# SuscoderSCH.net
KiCad netlist of a schematic drawn in Altium Designer
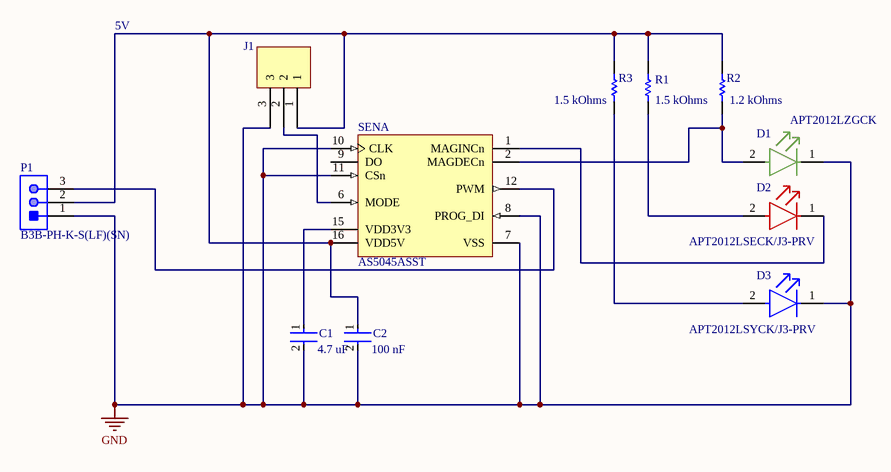
[diagram p0: SuscoderSCH.SchDoc]

(export (version "E")
  (design (tool "Eeschema 10.0.6"))
  (components
    (comp (ref "C1")
      (value "CC0805KKX7R7BB475")
      (footprint "FP-CC0805-0_85-MFG")
      (description "CAP CER 4.7UF 16V X7R 0805")
      (fields
        (field (name "MANUFACTURER") "Yageo")
        (field (name "OCTOPART") "https://octopart.com/cc0805kkx7r7bb475-yageo-34429188")
        (field (name "CAPACITANCE") "4.7 uF")
      )
      (libsource (lib "Altium Content Vault") (part "11868f565c42a9108669ba33697ecf6"))
    )
    (comp (ref "C2")
      (value "CC0805KRX7R7BB104")
      (footprint "FP-CC0805-0_85-MFG")
      (description "CAP CER 0.1UF 16V X7R 0805")
      (fields
        (field (name "MANUFACTURER") "Yageo")
        (field (name "OCTOPART") "https://octopart.com/cc0805krx7r7bb104-yageo-39467769")
        (field (name "CAPACITANCE") "100 nF")
      )
      (libsource (lib "Altium Content Vault") (part "11868f565c42a9108669ba33697ecf6"))
    )
    (comp (ref "D1")
      (value "APT2012LZGCK")
      (footprint "FP-APT2012LSYCK-J3-PRV-MFG")
      (description "2.0X1.2mm Low Current Green SMD LED; Water Clear; 525nm; 140° Viewing Angle")
      (libsource (lib "FRC2021 - #604") (part "8706943c75ba83719d021d2fdc84c58"))
    )
    (comp (ref "D2")
      (value "APT2012LSECK/J3-PRV")
      (footprint "FP-APT2012LSYCK-J3-PRV-MFG")
      (description "2.0X1.2mm Low Current Red SMD LED; Water Clear; 625nm; 140° Viewing Angle")
      (libsource (lib "FRC2021 - #604") (part "8706943c75ba83719d021d2fdc84c58"))
    )
    (comp (ref "D3")
      (value "APT2012LSYCK/J3-PRV")
      (footprint "FP-APT2012LSYCK-J3-PRV-MFG")
      (description "LED YELLOW CLEAR 2SMD")
      (fields
        (field (name "MANUFACTURER") "Kingbright")
        (field (name "OCTOPART") "https://octopart.com/apt2012lsyck%2Fj3-prv-kingbright-56784114")
      )
      (libsource (lib "Altium Content Vault") (part "8706943c75ba83719d021d2fdc84c58"))
    )
    (comp (ref "J1")
      (value "Tri-Pad Jumper")
      (footprint "Tri-Pad Jumper-Footprint-1")
      (description "A jumper with 3 pads.")
      (libsource (lib "FRC2021 - #604") (part "Tri-Pad Jumper-Symbol-1"))
    )
    (comp (ref "P1")
      (value "B3B-PH-K-S(LF)(SN)")
      (footprint "JST-B3B-PH-K-S-3_V")
      (fields (field (name "MANUFACTURER") "JST"))
      (libsource (lib "Altium Content Vault") (part "CN-1P-M-R3"))
    )
    (comp (ref "R1")
      (value "ERJ-6ENF1501V")
      (footprint "RESC2013X70X40ML20T20")
      (fields (field (name "MANUFACTURER") "Panasonic") (field (name "RESISTANCE") "1.5 kOhms"))
      (libsource (lib "Altium Content Vault") (part "RES"))
    )
    (comp (ref "R2")
      (value "ERJ6ENF1201V")
      (footprint "RESC2013X70X40ML20T20")
      (fields (field (name "MANUFACTURER") "Panasonic") (field (name "RESISTANCE") "1.2 kOhms"))
      (libsource (lib "Altium Content Vault") (part "RES"))
    )
    (comp (ref "R3")
      (value "ERJ-6ENF1501V")
      (footprint "RESC2013X70X40ML20T20")
      (fields (field (name "MANUFACTURER") "Panasonic") (field (name "RESISTANCE") "1.5 kOhms"))
      (libsource (lib "Altium Content Vault") (part "RES"))
    )
    (comp (ref "SEN")
      (value "AS5045ASST")
      (footprint "AMS-SSOP-16-6200X5300DE_A_N")
      (description "12 Bit Programmable Magnetic Rotary Encoder, 3.3 or 5 V, SSOP-16, Pb-Free, Reel")
      (fields (field (name "MANUFACTURER") "AMS"))
      (libsource (lib "Altium Content Vault") (part "AMS-AS5045-SSOP-16"))
    )
  )
  (nets
    (net (code "1") (name "GND") (class "Default")
      (node (ref "C1") (pin "2") (pinfunction "2_2") (pintype "passive"))
      (node (ref "C2") (pin "2") (pinfunction "2_2") (pintype "passive"))
      (node (ref "D1") (pin "1") (pinfunction "C_1") (pintype "passive"))
      (node (ref "D3") (pin "1") (pinfunction "C_1") (pintype "passive"))
      (node (ref "J1") (pin "3") (pinfunction "3_3") (pintype "passive"))
      (node (ref "P1") (pin "1") (pinfunction "1_1") (pintype "passive"))
      (node (ref "SEN") (pin "10") (pinfunction "CLK_10") (pintype "input"))
      (node (ref "SEN") (pin "11") (pinfunction "CSn_11") (pintype "input"))
      (node (ref "SEN") (pin "7") (pinfunction "VSS_7") (pintype "power_in"))
      (node (ref "SEN") (pin "8") (pinfunction "PROG_DI_8") (pintype "input"))
    )
    (net (code "2") (name "Net-(D1-A)") (class "Default")
      (node (ref "D1") (pin "2") (pinfunction "A_2") (pintype "passive"))
      (node (ref "R2") (pin "1") (pinfunction "1_1") (pintype "passive"))
      (node (ref "SEN") (pin "2") (pinfunction "MAGDECn_2") (pintype "open_collector"))
    )
    (net (code "3") (name "Net-(D2-A)") (class "Default")
      (node (ref "D2") (pin "2") (pinfunction "A_2") (pintype "passive"))
      (node (ref "R1") (pin "1") (pinfunction "1_1") (pintype "passive"))
    )
    (net (code "4") (name "Net-(D2-C)") (class "Default")
      (node (ref "D2") (pin "1") (pinfunction "C_1") (pintype "passive"))
      (node (ref "SEN") (pin "1") (pinfunction "MAGINCn_1") (pintype "open_collector"))
    )
    (net (code "5") (name "Net-(D3-A)") (class "Default")
      (node (ref "D3") (pin "2") (pinfunction "A_2") (pintype "passive"))
      (node (ref "R3") (pin "1") (pinfunction "1_1") (pintype "passive"))
    )
    (net (code "6") (name "Net-(SENA-MODE)") (class "Default")
      (node (ref "J1") (pin "2") (pinfunction "2_2") (pintype "passive"))
      (node (ref "SEN") (pin "6") (pinfunction "MODE_6") (pintype "input"))
    )
    (net (code "7") (name "Net-(SENA-PWM)") (class "Default")
      (node (ref "P1") (pin "3") (pinfunction "3_3") (pintype "passive"))
      (node (ref "SEN") (pin "12") (pinfunction "PWM_12") (pintype "output"))
    )
    (net (code "8") (name "Net-(SENA-VDD3V3)") (class "Default")
      (node (ref "C1") (pin "1") (pinfunction "1_1") (pintype "passive"))
      (node (ref "SEN") (pin "15") (pinfunction "VDD3V3_15") (pintype "power_in"))
    )
    (net (code "9") (name "Net-(SENA-VDD5V)") (class "Default")
      (node (ref "C2") (pin "1") (pinfunction "1_1") (pintype "passive"))
      (node (ref "J1") (pin "1") (pinfunction "1_1") (pintype "passive"))
      (node (ref "P1") (pin "2") (pinfunction "2_2") (pintype "passive"))
      (node (ref "R1") (pin "2") (pinfunction "2_2") (pintype "passive"))
      (node (ref "R2") (pin "2") (pinfunction "2_2") (pintype "passive"))
      (node (ref "R3") (pin "2") (pinfunction "2_2") (pintype "passive"))
      (node (ref "SEN") (pin "16") (pinfunction "VDD5V_16") (pintype "power_in"))
    )
    (net (code "10") (name "unconnected-(SENA-DO-Pad9)") (class "Default")
      (node (ref "SEN") (pin "9") (pinfunction "DO_9") (pintype "tri_state"))
    )
  )
)
